# au6850_mp3.net
KiCad netlist of a schematic drawn in EAGLE
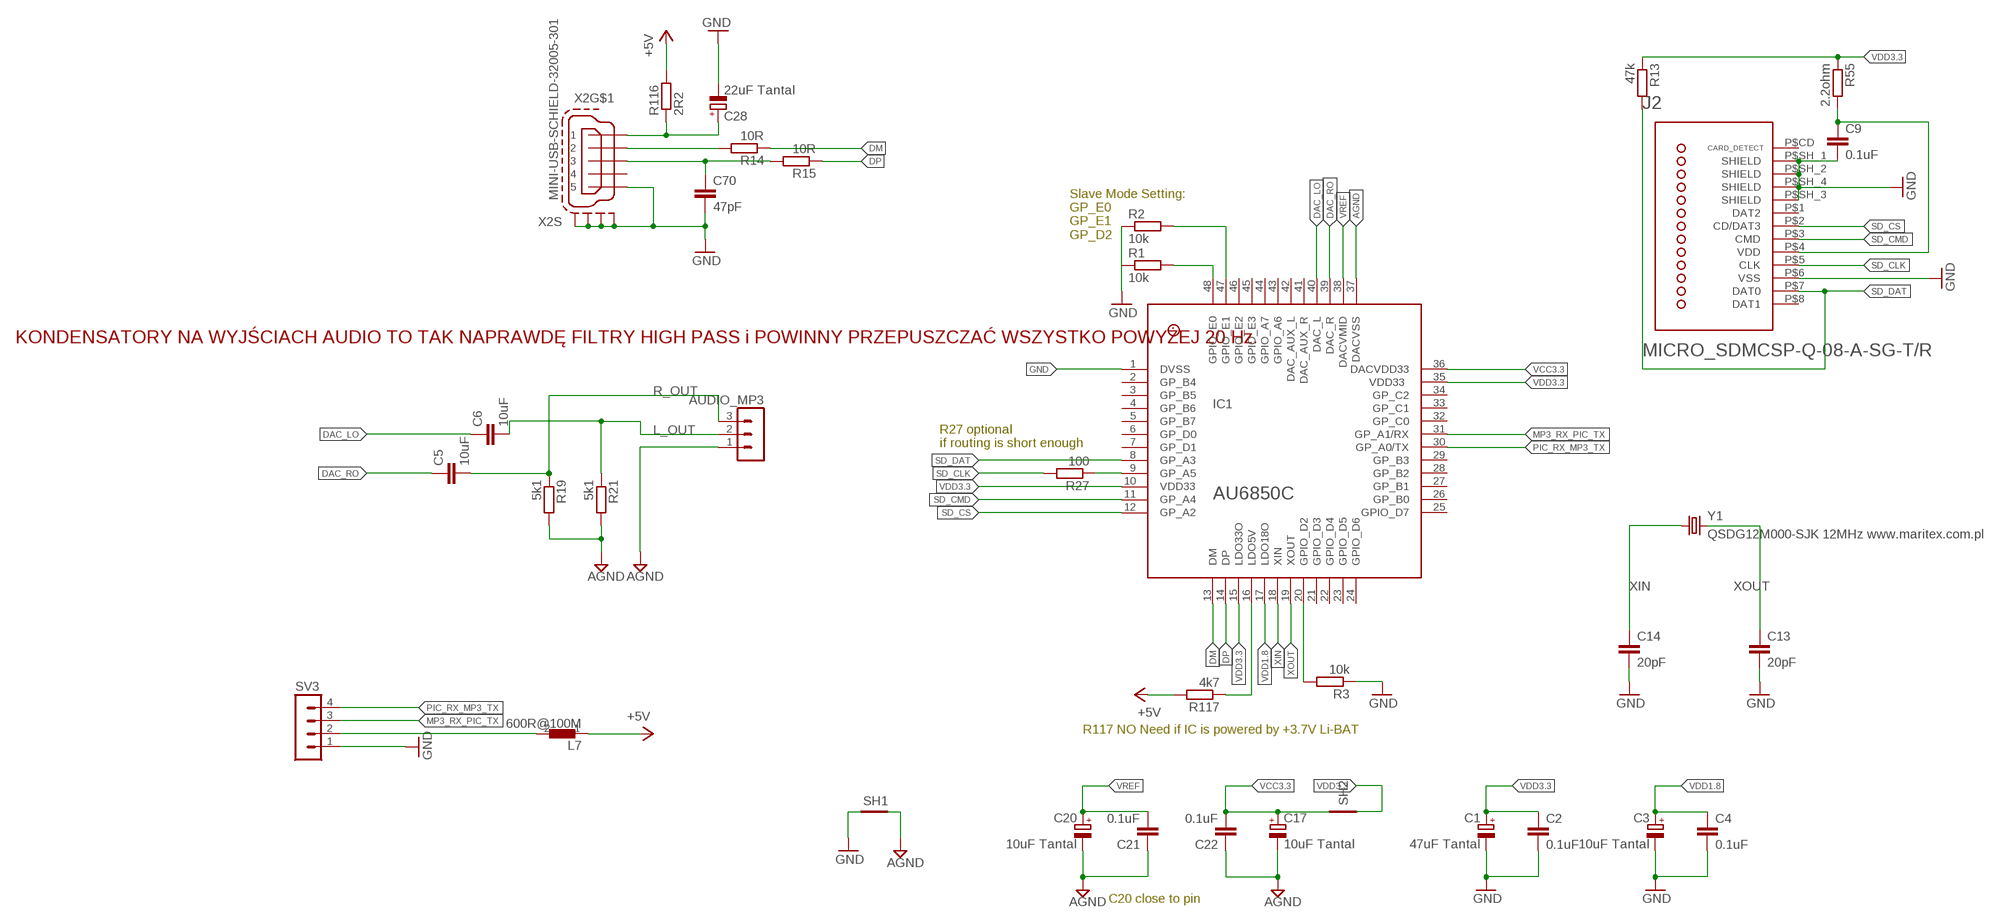
[diagram p0: schematic, sheet 1]

(export (version "E")
  (design (tool "Eeschema 10.0.6"))
  (components
    (comp (ref "AUDIO_MP3")
      (value "MA03-1")
      (footprint "eagle-import:MA03-1")
      (libsource (lib "eagle-import") (part "MA03-1"))
    )
    (comp (ref "C1")
      (value "47uF Tantal")
      (footprint "eagle-import:B_3528-21R")
      (libsource (lib "eagle-import") (part "CPOL-EUB/3528-21R"))
    )
    (comp (ref "C2")
      (value "0.1uF")
      (footprint "eagle-import:C0805")
      (libsource (lib "eagle-import") (part "C-EUC0805"))
    )
    (comp (ref "C3")
      (value "10uF Tantal")
      (footprint "eagle-import:B_3528-21R")
      (libsource (lib "eagle-import") (part "CPOL-EUB/3528-21R"))
    )
    (comp (ref "C4")
      (value "0.1uF")
      (footprint "eagle-import:C0805")
      (libsource (lib "eagle-import") (part "C-EUC0805"))
    )
    (comp (ref "C5")
      (value "10uF")
      (footprint "eagle-import:C0805")
      (libsource (lib "eagle-import") (part "C-EUC0805"))
    )
    (comp (ref "C6")
      (value "10uF")
      (footprint "eagle-import:C0805")
      (libsource (lib "eagle-import") (part "C-EUC0805"))
    )
    (comp (ref "C9")
      (value "0.1uF")
      (footprint "eagle-import:C0805")
      (libsource (lib "eagle-import") (part "resistor_C-EUC0805"))
    )
    (comp (ref "C13")
      (value "20pF")
      (footprint "eagle-import:C0805")
      (libsource (lib "eagle-import") (part "resistor_C-EUC0805"))
    )
    (comp (ref "C14")
      (value "20pF")
      (footprint "eagle-import:C0805")
      (libsource (lib "eagle-import") (part "resistor_C-EUC0805"))
    )
    (comp (ref "C17")
      (value "10uF Tantal")
      (footprint "eagle-import:B_3528-21R")
      (libsource (lib "eagle-import") (part "CPOL-EUB/3528-21R"))
    )
    (comp (ref "C20")
      (value "10uF Tantal")
      (footprint "eagle-import:B_3528-21R")
      (libsource (lib "eagle-import") (part "CPOL-EUB/3528-21R"))
    )
    (comp (ref "C21")
      (value "0.1uF")
      (footprint "eagle-import:C0805")
      (libsource (lib "eagle-import") (part "C-EUC0805"))
    )
    (comp (ref "C22")
      (value "0.1uF")
      (footprint "eagle-import:C0805")
      (libsource (lib "eagle-import") (part "C-EUC0805"))
    )
    (comp (ref "C28")
      (value "22uF Tantal")
      (footprint "eagle-import:SMC_A")
      (libsource (lib "eagle-import") (part "CPOL-EUSMCA"))
    )
    (comp (ref "C70")
      (value "47pF")
      (footprint "eagle-import:C0805")
      (libsource (lib "eagle-import") (part "resistor_C-EUC0805"))
    )
    (comp (ref "IC1")
      (value "AU6850C")
      (footprint "eagle-import:LQFP48-7X7")
      (libsource (lib "eagle-import") (part "AU6850C"))
    )
    (comp (ref "J2")
      (value "MICRO_SDMCSP-Q-08-A-SG-T/R")
      (footprint "eagle-import:MICRO_SD_8PINS")
      (libsource (lib "eagle-import") (part "MICRO_SDMCSP-Q-08-A-SG-T/R"))
    )
    (comp (ref "L7")
      (value "600R@100M")
      (footprint "eagle-import:R0805")
      (libsource (lib "eagle-import") (part "FERRITR0805"))
    )
    (comp (ref "R1")
      (value "10k")
      (footprint "eagle-import:R0805")
      (libsource (lib "eagle-import") (part "R-EU_R0805"))
    )
    (comp (ref "R2")
      (value "10k")
      (footprint "eagle-import:R0805")
      (libsource (lib "eagle-import") (part "R-EU_R0805"))
    )
    (comp (ref "R3")
      (value "10k")
      (footprint "eagle-import:R0805")
      (libsource (lib "eagle-import") (part "R-EU_R0805"))
    )
    (comp (ref "R13")
      (value "47k")
      (footprint "eagle-import:R0805")
      (libsource (lib "eagle-import") (part "R-EU_R0805"))
    )
    (comp (ref "R14")
      (value "10R")
      (footprint "eagle-import:R0805")
      (libsource (lib "eagle-import") (part "R-EU_R0805"))
    )
    (comp (ref "R15")
      (value "10R")
      (footprint "eagle-import:R0805")
      (libsource (lib "eagle-import") (part "R-EU_R0805"))
    )
    (comp (ref "R19")
      (value "5k1")
      (footprint "eagle-import:R0805")
      (libsource (lib "eagle-import") (part "R-EU_R0805"))
    )
    (comp (ref "R21")
      (value "5k1")
      (footprint "eagle-import:R0805")
      (libsource (lib "eagle-import") (part "R-EU_R0805"))
    )
    (comp (ref "R27")
      (value "100")
      (footprint "eagle-import:R0805")
      (libsource (lib "eagle-import") (part "R-EU_R0805"))
    )
    (comp (ref "R55")
      (value "2.2ohm")
      (footprint "eagle-import:R0805")
      (libsource (lib "eagle-import") (part "R-EU_R0805"))
    )
    (comp (ref "R116")
      (value "2R2")
      (footprint "eagle-import:R0805")
      (libsource (lib "eagle-import") (part "R-EU_R0805"))
    )
    (comp (ref "R117")
      (value "4k7")
      (footprint "eagle-import:R0805")
      (libsource (lib "eagle-import") (part "R-EU_R0805"))
    )
    (comp (ref "SH1")
      (value "SHORT-HT5")
      (footprint "eagle-import:SHORT_TOP-50")
      (libsource (lib "eagle-import") (part "SHORT-HT5"))
    )
    (comp (ref "SH2")
      (value "SHORT-V12_MILS")
      (footprint "eagle-import:12_MILS")
      (libsource (lib "eagle-import") (part "SHORT-V12_MILS"))
    )
    (comp (ref "SV3")
      (value "MA04-1")
      (footprint "eagle-import:MA04-1")
      (libsource (lib "eagle-import") (part "MA04-1"))
    )
    (comp (ref "X2")
      (value "MINI-USB-SCHIELD-32005-301")
      (footprint "eagle-import:32005-301")
      (libsource (lib "eagle-import") (part "MINI-USB-SCHIELD-32005-301"))
    )
    (comp (ref "Y1")
      (value "QSDG12M000-SJK 12MHz www.maritex.com.pl")
      (footprint "eagle-import:CRYSTAL-TXC-7A")
      (libsource (lib "eagle-import") (part "CRYSTALTXC-7A"))
    )
  )
  (nets
    (net (code "1") (name "+5V") (class "Default")
      (node (ref "L7") (pin "1") (pinfunction "1_1") (pintype "passive"))
      (node (ref "R116") (pin "2") (pinfunction "2_2") (pintype "passive"))
      (node (ref "R117") (pin "2") (pinfunction "2_2") (pintype "passive"))
    )
    (net (code "2") (name "/L_OUT") (class "Default")
      (node (ref "AUDIO_MP3") (pin "2") (pinfunction "2_2") (pintype "passive"))
      (node (ref "C6") (pin "2") (pinfunction "2_2") (pintype "passive"))
      (node (ref "R21") (pin "1") (pinfunction "1_1") (pintype "passive"))
    )
    (net (code "3") (name "/R_OUT") (class "Default")
      (node (ref "AUDIO_MP3") (pin "3") (pinfunction "3_3") (pintype "passive"))
      (node (ref "C5") (pin "2") (pinfunction "2_2") (pintype "passive"))
      (node (ref "R19") (pin "1") (pinfunction "1_1") (pintype "passive"))
    )
    (net (code "4") (name "AGND") (class "Default")
      (node (ref "AUDIO_MP3") (pin "1") (pinfunction "1_1") (pintype "passive"))
      (node (ref "C17") (pin "-") (pinfunction "-_-") (pintype "passive"))
      (node (ref "C20") (pin "-") (pinfunction "-_-") (pintype "passive"))
      (node (ref "C21") (pin "1") (pinfunction "1_1") (pintype "passive"))
      (node (ref "C22") (pin "1") (pinfunction "1_1") (pintype "passive"))
      (node (ref "IC1") (pin "37") (pinfunction "DACVSS_37") (pintype "input"))
      (node (ref "R19") (pin "2") (pinfunction "2_2") (pintype "passive"))
      (node (ref "R21") (pin "2") (pinfunction "2_2") (pintype "passive"))
      (node (ref "SH1") (pin "2") (pinfunction "P$2_2") (pintype "bidirectional"))
    )
    (net (code "5") (name "DAC_LO") (class "Default")
      (node (ref "C6") (pin "1") (pinfunction "1_1") (pintype "passive"))
      (node (ref "IC1") (pin "40") (pinfunction "DAC_L_40") (pintype "output"))
    )
    (net (code "6") (name "DAC_RO") (class "Default")
      (node (ref "C5") (pin "1") (pinfunction "1_1") (pintype "passive"))
      (node (ref "IC1") (pin "39") (pinfunction "DAC_R_39") (pintype "output"))
    )
    (net (code "7") (name "DM") (class "Default")
      (node (ref "IC1") (pin "13") (pinfunction "DM_13") (pintype "bidirectional"))
      (node (ref "R14") (pin "1") (pinfunction "1_1") (pintype "passive"))
    )
    (net (code "8") (name "DP") (class "Default")
      (node (ref "IC1") (pin "14") (pinfunction "DP_14") (pintype "bidirectional"))
      (node (ref "R15") (pin "1") (pinfunction "1_1") (pintype "passive"))
    )
    (net (code "9") (name "GND") (class "Default")
      (node (ref "C1") (pin "-") (pinfunction "-_-") (pintype "passive"))
      (node (ref "C13") (pin "2") (pinfunction "2_2") (pintype "passive"))
      (node (ref "C14") (pin "2") (pinfunction "2_2") (pintype "passive"))
      (node (ref "C2") (pin "2") (pinfunction "2_2") (pintype "passive"))
      (node (ref "C28") (pin "-") (pinfunction "-_-") (pintype "passive"))
      (node (ref "C3") (pin "-") (pinfunction "-_-") (pintype "passive"))
      (node (ref "C4") (pin "2") (pinfunction "2_2") (pintype "passive"))
      (node (ref "C70") (pin "2") (pinfunction "2_2") (pintype "passive"))
      (node (ref "C9") (pin "2") (pinfunction "2_2") (pintype "passive"))
      (node (ref "IC1") (pin "1") (pinfunction "DVSS_1") (pintype "bidirectional"))
      (node (ref "J2") (pin "P$6") (pinfunction "VSS_P$6") (pintype "bidirectional"))
      (node (ref "J2") (pin "P$SH_1") (pinfunction "1_GND_PAD_P$SH_1") (pintype "bidirectional"))
      (node (ref "J2") (pin "P$SH_2") (pinfunction "2_GND_PAD_P$SH_2") (pintype "bidirectional"))
      (node (ref "J2") (pin "P$SH_3") (pinfunction "3_GND_PAD_P$SH_3") (pintype "bidirectional"))
      (node (ref "J2") (pin "P$SH_4") (pinfunction "4_GND_PAD_P$SH_4") (pintype "bidirectional"))
      (node (ref "R1") (pin "1") (pinfunction "1_1") (pintype "passive"))
      (node (ref "R2") (pin "1") (pinfunction "1_1") (pintype "passive"))
      (node (ref "R3") (pin "1") (pinfunction "1_1") (pintype "passive"))
      (node (ref "SH1") (pin "1") (pinfunction "P$1_1") (pintype "bidirectional"))
      (node (ref "SV3") (pin "1") (pinfunction "1_1") (pintype "passive"))
      (node (ref "X2") (pin "5") (pinfunction "5_5") (pintype "passive"))
      (node (ref "X2") (pin "M1") (pinfunction "S1_M1") (pintype "passive"))
      (node (ref "X2") (pin "M2") (pinfunction "S2_M2") (pintype "passive"))
      (node (ref "X2") (pin "M3") (pinfunction "S3_M3") (pintype "passive"))
      (node (ref "X2") (pin "M4") (pinfunction "S4_M4") (pintype "passive"))
    )
    (net (code "10") (name "MP3_RX_PIC_TX") (class "Default")
      (node (ref "IC1") (pin "31") (pinfunction "GP_A1/RX_31") (pintype "bidirectional"))
      (node (ref "SV3") (pin "3") (pinfunction "3_3") (pintype "passive"))
    )
    (net (code "11") (name "Net-(C28-Pad+)") (class "Default")
      (node (ref "C28") (pin "+") (pinfunction "+_+") (pintype "passive"))
      (node (ref "R116") (pin "1") (pinfunction "1_1") (pintype "passive"))
      (node (ref "X2") (pin "1") (pinfunction "1_1") (pintype "passive"))
    )
    (net (code "12") (name "Net-(C70-Pad1)") (class "Default")
      (node (ref "C70") (pin "1") (pinfunction "1_1") (pintype "passive"))
      (node (ref "R15") (pin "2") (pinfunction "2_2") (pintype "passive"))
      (node (ref "X2") (pin "3") (pinfunction "3_3") (pintype "passive"))
    )
    (net (code "13") (name "Net-(IC1-GPIO_D2)") (class "Default")
      (node (ref "IC1") (pin "20") (pinfunction "GPIO_D2_20") (pintype "bidirectional"))
      (node (ref "R3") (pin "2") (pinfunction "2_2") (pintype "passive"))
    )
    (net (code "14") (name "Net-(IC1-GPIO_E0)") (class "Default")
      (node (ref "IC1") (pin "48") (pinfunction "GPIO_E0_48") (pintype "bidirectional"))
      (node (ref "R1") (pin "2") (pinfunction "2_2") (pintype "passive"))
    )
    (net (code "15") (name "Net-(IC1-GPIO_E1)") (class "Default")
      (node (ref "IC1") (pin "47") (pinfunction "GPIO_E1_47") (pintype "bidirectional"))
      (node (ref "R2") (pin "2") (pinfunction "2_2") (pintype "passive"))
    )
    (net (code "16") (name "Net-(IC1-GP_A5)") (class "Default")
      (node (ref "IC1") (pin "9") (pinfunction "GP_A5_9") (pintype "bidirectional"))
      (node (ref "R27") (pin "1") (pinfunction "1_1") (pintype "passive"))
    )
    (net (code "17") (name "Net-(IC1-LDO5V)") (class "Default")
      (node (ref "IC1") (pin "16") (pinfunction "LDO5V_16") (pintype "bidirectional"))
      (node (ref "R117") (pin "1") (pinfunction "1_1") (pintype "passive"))
    )
    (net (code "18") (name "Net-(J2-VDD)") (class "Default")
      (node (ref "C9") (pin "1") (pinfunction "1_1") (pintype "passive"))
      (node (ref "J2") (pin "P$4") (pinfunction "VDD_P$4") (pintype "bidirectional"))
      (node (ref "R55") (pin "2") (pinfunction "2_2") (pintype "passive"))
    )
    (net (code "19") (name "Net-(L7-Pad2)") (class "Default")
      (node (ref "L7") (pin "2") (pinfunction "2_2") (pintype "passive"))
      (node (ref "SV3") (pin "2") (pinfunction "2_2") (pintype "passive"))
    )
    (net (code "20") (name "Net-(R14-Pad2)") (class "Default")
      (node (ref "R14") (pin "2") (pinfunction "2_2") (pintype "passive"))
      (node (ref "X2") (pin "2") (pinfunction "2_2") (pintype "passive"))
    )
    (net (code "21") (name "PIC_RX_MP3_TX") (class "Default")
      (node (ref "IC1") (pin "30") (pinfunction "GP_A0/TX_30") (pintype "bidirectional"))
      (node (ref "SV3") (pin "4") (pinfunction "4_4") (pintype "passive"))
    )
    (net (code "22") (name "SD_CLK") (class "Default")
      (node (ref "J2") (pin "P$5") (pinfunction "CLK_P$5") (pintype "bidirectional"))
      (node (ref "R27") (pin "2") (pinfunction "2_2") (pintype "passive"))
    )
    (net (code "23") (name "SD_CMD") (class "Default")
      (node (ref "IC1") (pin "11") (pinfunction "GP_A4_11") (pintype "bidirectional"))
      (node (ref "J2") (pin "P$3") (pinfunction "CMD_P$3") (pintype "bidirectional"))
    )
    (net (code "24") (name "SD_CS") (class "Default")
      (node (ref "IC1") (pin "12") (pinfunction "GP_A2_12") (pintype "bidirectional"))
      (node (ref "J2") (pin "P$2") (pinfunction "CD/DAT3_P$2") (pintype "bidirectional"))
    )
    (net (code "25") (name "SD_DAT") (class "Default")
      (node (ref "IC1") (pin "8") (pinfunction "GP_A3_8") (pintype "bidirectional"))
      (node (ref "J2") (pin "P$7") (pinfunction "DAT0_P$7") (pintype "bidirectional"))
      (node (ref "R13") (pin "2") (pinfunction "2_2") (pintype "passive"))
    )
    (net (code "26") (name "VCC3.3") (class "Default")
      (node (ref "C17") (pin "+") (pinfunction "+_+") (pintype "passive"))
      (node (ref "C22") (pin "2") (pinfunction "2_2") (pintype "passive"))
      (node (ref "IC1") (pin "36") (pinfunction "DACVDD33_36") (pintype "input"))
      (node (ref "SH2") (pin "P$2") (pinfunction "P$2_P$2") (pintype "bidirectional"))
    )
    (net (code "27") (name "VDD1.8") (class "Default")
      (node (ref "C3") (pin "+") (pinfunction "+_+") (pintype "passive"))
      (node (ref "C4") (pin "1") (pinfunction "1_1") (pintype "passive"))
      (node (ref "IC1") (pin "17") (pinfunction "LDO18O_17") (pintype "bidirectional"))
    )
    (net (code "28") (name "VDD3.3") (class "Default")
      (node (ref "C1") (pin "+") (pinfunction "+_+") (pintype "passive"))
      (node (ref "C2") (pin "1") (pinfunction "1_1") (pintype "passive"))
      (node (ref "IC1") (pin "10") (pinfunction "VDD33_10") (pintype "power_in"))
      (node (ref "IC1") (pin "15") (pinfunction "LDO33O_15") (pintype "output"))
      (node (ref "IC1") (pin "35") (pinfunction "VDD33_35") (pintype "input"))
      (node (ref "R13") (pin "1") (pinfunction "1_1") (pintype "passive"))
      (node (ref "R55") (pin "1") (pinfunction "1_1") (pintype "passive"))
      (node (ref "SH2") (pin "P$1") (pinfunction "P$1_P$1") (pintype "bidirectional"))
    )
    (net (code "29") (name "VREF") (class "Default")
      (node (ref "C20") (pin "+") (pinfunction "+_+") (pintype "passive"))
      (node (ref "C21") (pin "2") (pinfunction "2_2") (pintype "passive"))
      (node (ref "IC1") (pin "38") (pinfunction "DACVMID_38") (pintype "input"))
    )
    (net (code "30") (name "XIN") (class "Default")
      (node (ref "C14") (pin "1") (pinfunction "1_1") (pintype "passive"))
      (node (ref "IC1") (pin "18") (pinfunction "XIN_18") (pintype "input"))
      (node (ref "Y1") (pin "P$1") (pinfunction "1_P$1") (pintype "passive"))
    )
    (net (code "31") (name "XOUT") (class "Default")
      (node (ref "C13") (pin "1") (pinfunction "1_1") (pintype "passive"))
      (node (ref "IC1") (pin "19") (pinfunction "XOUT_19") (pintype "output"))
      (node (ref "Y1") (pin "P$2") (pinfunction "2_P$2") (pintype "passive"))
    )
    (net (code "32") (name "unconnected-(IC1-DAC_AUX_L-Pad42)") (class "Default")
      (node (ref "IC1") (pin "42") (pinfunction "DAC_AUX_L_42") (pintype "input"))
    )
    (net (code "33") (name "unconnected-(IC1-DAC_AUX_R-Pad41)") (class "Default")
      (node (ref "IC1") (pin "41") (pinfunction "DAC_AUX_R_41") (pintype "input"))
    )
    (net (code "34") (name "unconnected-(IC1-GPIO_A6-Pad43)") (class "Default")
      (node (ref "IC1") (pin "43") (pinfunction "GPIO_A6_43") (pintype "bidirectional"))
    )
    (net (code "35") (name "unconnected-(IC1-GPIO_A7-Pad44)") (class "Default")
      (node (ref "IC1") (pin "44") (pinfunction "GPIO_A7_44") (pintype "bidirectional"))
    )
    (net (code "36") (name "unconnected-(IC1-GPIO_D3-Pad21)") (class "Default")
      (node (ref "IC1") (pin "21") (pinfunction "GPIO_D3_21") (pintype "bidirectional"))
    )
    (net (code "37") (name "unconnected-(IC1-GPIO_D4-Pad22)") (class "Default")
      (node (ref "IC1") (pin "22") (pinfunction "GPIO_D4_22") (pintype "bidirectional"))
    )
    (net (code "38") (name "unconnected-(IC1-GPIO_D5-Pad23)") (class "Default")
      (node (ref "IC1") (pin "23") (pinfunction "GPIO_D5_23") (pintype "bidirectional"))
    )
    (net (code "39") (name "unconnected-(IC1-GPIO_D6-Pad24)") (class "Default")
      (node (ref "IC1") (pin "24") (pinfunction "GPIO_D6_24") (pintype "bidirectional"))
    )
    (net (code "40") (name "unconnected-(IC1-GPIO_D7-Pad25)") (class "Default")
      (node (ref "IC1") (pin "25") (pinfunction "GPIO_D7_25") (pintype "bidirectional"))
    )
    (net (code "41") (name "unconnected-(IC1-GPIO_E2-Pad46)") (class "Default")
      (node (ref "IC1") (pin "46") (pinfunction "GPIO_E2_46") (pintype "bidirectional"))
    )
    (net (code "42") (name "unconnected-(IC1-GPIO_E3-Pad45)") (class "Default")
      (node (ref "IC1") (pin "45") (pinfunction "GPIO_E3_45") (pintype "bidirectional"))
    )
    (net (code "43") (name "unconnected-(IC1-GP_B0-Pad26)") (class "Default")
      (node (ref "IC1") (pin "26") (pinfunction "GP_B0_26") (pintype "bidirectional"))
    )
    (net (code "44") (name "unconnected-(IC1-GP_B1-Pad27)") (class "Default")
      (node (ref "IC1") (pin "27") (pinfunction "GP_B1_27") (pintype "bidirectional"))
    )
    (net (code "45") (name "unconnected-(IC1-GP_B2-Pad28)") (class "Default")
      (node (ref "IC1") (pin "28") (pinfunction "GP_B2_28") (pintype "bidirectional"))
    )
    (net (code "46") (name "unconnected-(IC1-GP_B3-Pad29)") (class "Default")
      (node (ref "IC1") (pin "29") (pinfunction "GP_B3_29") (pintype "bidirectional"))
    )
    (net (code "47") (name "unconnected-(IC1-GP_B4-Pad2)") (class "Default")
      (node (ref "IC1") (pin "2") (pinfunction "GP_B4_2") (pintype "bidirectional"))
    )
    (net (code "48") (name "unconnected-(IC1-GP_B5-Pad3)") (class "Default")
      (node (ref "IC1") (pin "3") (pinfunction "GP_B5_3") (pintype "bidirectional"))
    )
    (net (code "49") (name "unconnected-(IC1-GP_B6-Pad4)") (class "Default")
      (node (ref "IC1") (pin "4") (pinfunction "GP_B6_4") (pintype "bidirectional"))
    )
    (net (code "50") (name "unconnected-(IC1-GP_B7-Pad5)") (class "Default")
      (node (ref "IC1") (pin "5") (pinfunction "GP_B7_5") (pintype "bidirectional"))
    )
    (net (code "51") (name "unconnected-(IC1-GP_C0-Pad32)") (class "Default")
      (node (ref "IC1") (pin "32") (pinfunction "GP_C0_32") (pintype "bidirectional"))
    )
    (net (code "52") (name "unconnected-(IC1-GP_C1-Pad33)") (class "Default")
      (node (ref "IC1") (pin "33") (pinfunction "GP_C1_33") (pintype "bidirectional"))
    )
    (net (code "53") (name "unconnected-(IC1-GP_C2-Pad34)") (class "Default")
      (node (ref "IC1") (pin "34") (pinfunction "GP_C2_34") (pintype "bidirectional"))
    )
    (net (code "54") (name "unconnected-(IC1-GP_D0-Pad6)") (class "Default")
      (node (ref "IC1") (pin "6") (pinfunction "GP_D0_6") (pintype "bidirectional"))
    )
    (net (code "55") (name "unconnected-(IC1-GP_D1-Pad7)") (class "Default")
      (node (ref "IC1") (pin "7") (pinfunction "GP_D1_7") (pintype "bidirectional"))
    )
    (net (code "56") (name "unconnected-(J2-CARD_DETECT_SW-PadP$CD)") (class "Default")
      (node (ref "J2") (pin "P$CD") (pinfunction "CARD_DETECT_SW_P$CD") (pintype "bidirectional"))
    )
    (net (code "57") (name "unconnected-(J2-DAT1-PadP$8)") (class "Default")
      (node (ref "J2") (pin "P$8") (pinfunction "DAT1_P$8") (pintype "bidirectional"))
    )
    (net (code "58") (name "unconnected-(J2-DAT2-PadP$1)") (class "Default")
      (node (ref "J2") (pin "P$1") (pinfunction "DAT2_P$1") (pintype "bidirectional"))
    )
    (net (code "59") (name "unconnected-(X2-Pad4)") (class "Default")
      (node (ref "X2") (pin "4") (pinfunction "4_4") (pintype "passive"))
    )
  )
)
